# MCU.net
KiCad netlist of a schematic drawn in Altium Designer
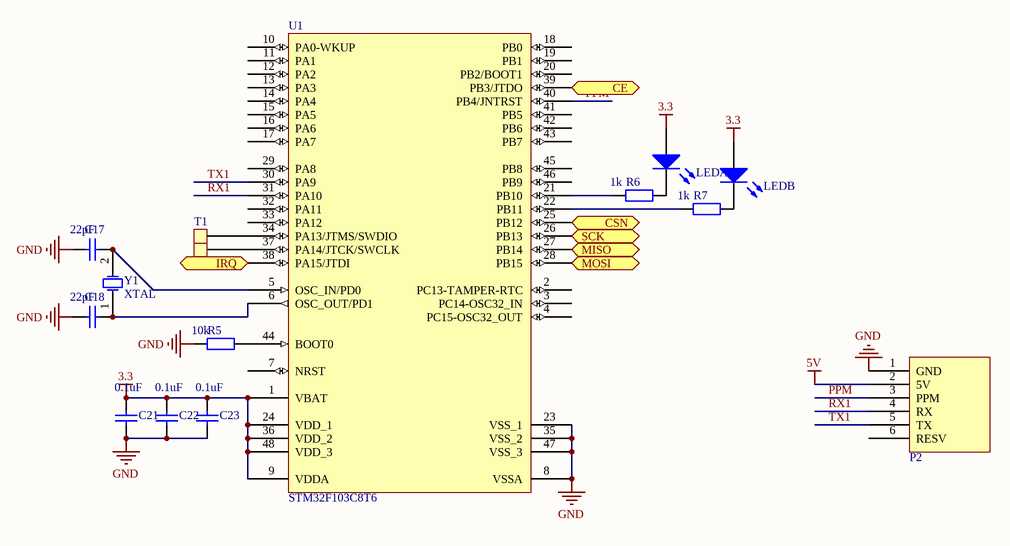
[diagram p0: MCU.SchDoc]

(export (version "E")
  (design (tool "Eeschema 10.0.6"))
  (components
    (comp (ref "C17")
      (value "22pF")
      (footprint "0402")
      (description "Capacitor")
      (fields (field (name "PUBLISHER") "Altium Limited"))
      (libsource (lib "RTC6705") (part "Cap"))
    )
    (comp (ref "C18")
      (value "22pF")
      (footprint "0402")
      (description "Capacitor")
      (fields (field (name "PUBLISHER") "Altium Limited"))
      (libsource (lib "RTC6705") (part "Cap"))
    )
    (comp (ref "C21")
      (value "0.1uF")
      (footprint "0402")
      (description "Capacitor")
      (fields (field (name "PUBLISHER") "Altium Limited"))
      (libsource (lib "RTC6705") (part "Cap"))
    )
    (comp (ref "C22")
      (value "0.1uF")
      (footprint "0402")
      (description "Capacitor")
      (fields (field (name "PUBLISHER") "Altium Limited"))
      (libsource (lib "RTC6705") (part "Cap"))
    )
    (comp (ref "C23")
      (value "0.1uF")
      (footprint "0402")
      (description "Capacitor")
      (fields (field (name "PUBLISHER") "Altium Limited"))
      (libsource (lib "RTC6705") (part "Cap"))
    )
    (comp (ref "LED")
      (value "LEDx2")
      (footprint "LC-0603_Rx2")
      (description "Typical RED GaAs LED")
      (fields (field (name "PUBLISHER") "Altium Limited"))
      (libsource (lib "sch") (part "LEDx2"))
    )
    (comp (ref "P2") (value "PPMInf") (footprint "PPMInf") (libsource (lib "NRF24L01_PA") (part "PPMInf")))
    (comp (ref "R5")
      (value "10k")
      (footprint "0402")
      (description "Resistor")
      (fields (field (name "PUBLISHER") "Altium Limited"))
      (libsource (lib "RTC6705") (part "Res2"))
    )
    (comp (ref "R6")
      (value "1k")
      (footprint "0402")
      (description "Resistor")
      (fields (field (name "PUBLISHER") "Altium Limited"))
      (libsource (lib "RTC6705") (part "Res2"))
    )
    (comp (ref "R7")
      (value "1k")
      (footprint "0402")
      (description "Resistor")
      (fields (field (name "PUBLISHER") "Altium Limited"))
      (libsource (lib "RTC6705") (part "Res2"))
    )
    (comp (ref "T1") (value "TestPad") (footprint "TestPad - 1mm") (libsource (lib "sch") (part "TestPad")))
    (comp (ref "T2") (value "TestPad") (footprint "TestPad - 1mm") (libsource (lib "sch") (part "TestPad")))
    (comp (ref "U1")
      (value "STM32F103C8T6")
      (footprint "LQFP48_L")
      (description "STM32 ARM-based 32-bit MCU with 64 Kbytes Flash, 48-pin LQFP, Industrial Temperature")
      (fields (field (name "PUBLISHER") "*"))
      (libsource (lib "ST Microcontroller 32-Bit STM32 SCH") (part "STM32F103C8T6"))
    )
    (comp (ref "Y1")
      (value "XTAL")
      (footprint "5032-crystal")
      (description "Crystal Oscillator")
      (fields (field (name "PUBLISHER") "Altium Limited"))
      (libsource (lib "Miscellaneous Devices") (part "XTAL"))
    )
  )
  (nets
    (net (code "1") (name "/CE") (class "Default")
      (node (ref "U1") (pin "39") (pinfunction "PB3/JTDO_39") (pintype "bidirectional"))
    )
    (net (code "2") (name "/CSN") (class "Default")
      (node (ref "U1") (pin "25") (pinfunction "PB12_25") (pintype "bidirectional"))
    )
    (net (code "3") (name "/IRQ") (class "Default")
      (node (ref "U1") (pin "38") (pinfunction "PA15/JTDI_38") (pintype "bidirectional"))
    )
    (net (code "4") (name "/MISO") (class "Default")
      (node (ref "U1") (pin "27") (pinfunction "PB14_27") (pintype "bidirectional"))
    )
    (net (code "5") (name "/MOSI") (class "Default")
      (node (ref "U1") (pin "28") (pinfunction "PB15_28") (pintype "bidirectional"))
    )
    (net (code "6") (name "/PPM") (class "Default")
      (node (ref "P2") (pin "3") (pinfunction "PPM_3") (pintype "passive"))
      (node (ref "U1") (pin "40") (pinfunction "PB4/JNTRST_40") (pintype "bidirectional"))
    )
    (net (code "7") (name "/RX1") (class "Default")
      (node (ref "P2") (pin "4") (pinfunction "RX_4") (pintype "passive"))
      (node (ref "U1") (pin "31") (pinfunction "PA10_31") (pintype "bidirectional"))
    )
    (net (code "8") (name "/SCK") (class "Default")
      (node (ref "U1") (pin "26") (pinfunction "PB13_26") (pintype "bidirectional"))
    )
    (net (code "9") (name "/TX1") (class "Default")
      (node (ref "P2") (pin "5") (pinfunction "TX_5") (pintype "passive"))
      (node (ref "U1") (pin "30") (pinfunction "PA9_30") (pintype "bidirectional"))
    )
    (net (code "10") (name "3.3") (class "Default")
      (node (ref "C21") (pin "1") (pinfunction "1_1") (pintype "passive"))
      (node (ref "C22") (pin "1") (pinfunction "1_1") (pintype "passive"))
      (node (ref "C23") (pin "1") (pinfunction "1_1") (pintype "passive"))
      (node (ref "LED") (pin "1") (pinfunction "A_1") (pintype "passive"))
      (node (ref "LED") (pin "2") (pinfunction "A_2") (pintype "passive"))
      (node (ref "U1") (pin "1") (pinfunction "VBAT_1") (pintype "power_in"))
      (node (ref "U1") (pin "24") (pinfunction "VDD_1_24") (pintype "power_in"))
      (node (ref "U1") (pin "36") (pinfunction "VDD_2_36") (pintype "power_in"))
      (node (ref "U1") (pin "48") (pinfunction "VDD_3_48") (pintype "power_in"))
      (node (ref "U1") (pin "9") (pinfunction "VDDA_9") (pintype "power_in"))
    )
    (net (code "11") (name "5V") (class "Default")
      (node (ref "P2") (pin "2") (pinfunction "5V_2") (pintype "passive"))
    )
    (net (code "12") (name "GND") (class "Default")
      (node (ref "C17") (pin "1") (pinfunction "1_1") (pintype "passive"))
      (node (ref "C18") (pin "1") (pinfunction "1_1") (pintype "passive"))
      (node (ref "C21") (pin "2") (pinfunction "2_2") (pintype "passive"))
      (node (ref "C22") (pin "2") (pinfunction "2_2") (pintype "passive"))
      (node (ref "C23") (pin "2") (pinfunction "2_2") (pintype "passive"))
      (node (ref "P2") (pin "1") (pinfunction "GND_1") (pintype "passive"))
      (node (ref "R5") (pin "1") (pinfunction "1_1") (pintype "passive"))
      (node (ref "U1") (pin "23") (pinfunction "VSS_1_23") (pintype "power_in"))
      (node (ref "U1") (pin "35") (pinfunction "VSS_2_35") (pintype "power_in"))
      (node (ref "U1") (pin "47") (pinfunction "VSS_3_47") (pintype "power_in"))
      (node (ref "U1") (pin "8") (pinfunction "VSSA_8") (pintype "power_in"))
    )
    (net (code "13") (name "Net-(LEDA-K)") (class "Default")
      (node (ref "LED") (pin "3") (pinfunction "K_3") (pintype "passive"))
      (node (ref "R6") (pin "2") (pinfunction "2_2") (pintype "passive"))
    )
    (net (code "14") (name "Net-(LEDB-K)") (class "Default")
      (node (ref "LED") (pin "4") (pinfunction "K_4") (pintype "passive"))
      (node (ref "R7") (pin "2") (pinfunction "2_2") (pintype "passive"))
    )
    (net (code "15") (name "Net-(T1-3)") (class "Default")
      (node (ref "T1") (pin "1") (pinfunction "3_1") (pintype "passive"))
      (node (ref "U1") (pin "34") (pinfunction "PA13/JTMS/SWDIO_34") (pintype "bidirectional"))
    )
    (net (code "16") (name "Net-(T2-3)") (class "Default")
      (node (ref "T2") (pin "1") (pinfunction "3_1") (pintype "passive"))
      (node (ref "U1") (pin "37") (pinfunction "PA14/JTCK/SWCLK_37") (pintype "bidirectional"))
    )
    (net (code "17") (name "Net-(U1-BOOT0)") (class "Default")
      (node (ref "R5") (pin "2") (pinfunction "2_2") (pintype "passive"))
      (node (ref "U1") (pin "44") (pinfunction "BOOT0_44") (pintype "input"))
    )
    (net (code "18") (name "Net-(U1-OSC_IN{slash}PD0)") (class "Default")
      (node (ref "C17") (pin "2") (pinfunction "2_2") (pintype "passive"))
      (node (ref "U1") (pin "5") (pinfunction "OSC_IN/PD0_5") (pintype "input"))
      (node (ref "Y1") (pin "2") (pinfunction "OSC2_2") (pintype "passive"))
    )
    (net (code "19") (name "Net-(U1-OSC_OUT{slash}PD1)") (class "Default")
      (node (ref "C18") (pin "2") (pinfunction "2_2") (pintype "passive"))
      (node (ref "U1") (pin "6") (pinfunction "OSC_OUT/PD1_6") (pintype "output"))
      (node (ref "Y1") (pin "1") (pinfunction "OSC1_1") (pintype "passive"))
    )
    (net (code "20") (name "Net-(U1-PB10)") (class "Default")
      (node (ref "R6") (pin "1") (pinfunction "1_1") (pintype "passive"))
      (node (ref "U1") (pin "21") (pinfunction "PB10_21") (pintype "bidirectional"))
    )
    (net (code "21") (name "Net-(U1-PB11)") (class "Default")
      (node (ref "R7") (pin "1") (pinfunction "1_1") (pintype "passive"))
      (node (ref "U1") (pin "22") (pinfunction "PB11_22") (pintype "bidirectional"))
    )
    (net (code "22") (name "unconnected-(P2-RESV-Pad6)") (class "Default")
      (node (ref "P2") (pin "6") (pinfunction "RESV_6") (pintype "passive"))
    )
    (net (code "23") (name "unconnected-(U1-NRST-Pad7)") (class "Default")
      (node (ref "U1") (pin "7") (pinfunction "NRST_7") (pintype "bidirectional"))
    )
    (net (code "24") (name "unconnected-(U1-PA0-WKUP-Pad10)") (class "Default")
      (node (ref "U1") (pin "10") (pinfunction "PA0-WKUP_10") (pintype "bidirectional"))
    )
    (net (code "25") (name "unconnected-(U1-PA1-Pad11)") (class "Default")
      (node (ref "U1") (pin "11") (pinfunction "PA1_11") (pintype "bidirectional"))
    )
    (net (code "26") (name "unconnected-(U1-PA2-Pad12)") (class "Default")
      (node (ref "U1") (pin "12") (pinfunction "PA2_12") (pintype "bidirectional"))
    )
    (net (code "27") (name "unconnected-(U1-PA3-Pad13)") (class "Default")
      (node (ref "U1") (pin "13") (pinfunction "PA3_13") (pintype "bidirectional"))
    )
    (net (code "28") (name "unconnected-(U1-PA4-Pad14)") (class "Default")
      (node (ref "U1") (pin "14") (pinfunction "PA4_14") (pintype "bidirectional"))
    )
    (net (code "29") (name "unconnected-(U1-PA5-Pad15)") (class "Default")
      (node (ref "U1") (pin "15") (pinfunction "PA5_15") (pintype "bidirectional"))
    )
    (net (code "30") (name "unconnected-(U1-PA6-Pad16)") (class "Default")
      (node (ref "U1") (pin "16") (pinfunction "PA6_16") (pintype "bidirectional"))
    )
    (net (code "31") (name "unconnected-(U1-PA7-Pad17)") (class "Default")
      (node (ref "U1") (pin "17") (pinfunction "PA7_17") (pintype "bidirectional"))
    )
    (net (code "32") (name "unconnected-(U1-PA8-Pad29)") (class "Default")
      (node (ref "U1") (pin "29") (pinfunction "PA8_29") (pintype "bidirectional"))
    )
    (net (code "33") (name "unconnected-(U1-PA11-Pad32)") (class "Default")
      (node (ref "U1") (pin "32") (pinfunction "PA11_32") (pintype "bidirectional"))
    )
    (net (code "34") (name "unconnected-(U1-PA12-Pad33)") (class "Default")
      (node (ref "U1") (pin "33") (pinfunction "PA12_33") (pintype "bidirectional"))
    )
    (net (code "35") (name "unconnected-(U1-PB0-Pad18)") (class "Default")
      (node (ref "U1") (pin "18") (pinfunction "PB0_18") (pintype "bidirectional"))
    )
    (net (code "36") (name "unconnected-(U1-PB1-Pad19)") (class "Default")
      (node (ref "U1") (pin "19") (pinfunction "PB1_19") (pintype "bidirectional"))
    )
    (net (code "37") (name "unconnected-(U1-PB2{slash}BOOT1-Pad20)") (class "Default")
      (node (ref "U1") (pin "20") (pinfunction "PB2/BOOT1_20") (pintype "bidirectional"))
    )
    (net (code "38") (name "unconnected-(U1-PB5-Pad41)") (class "Default")
      (node (ref "U1") (pin "41") (pinfunction "PB5_41") (pintype "bidirectional"))
    )
    (net (code "39") (name "unconnected-(U1-PB6-Pad42)") (class "Default")
      (node (ref "U1") (pin "42") (pinfunction "PB6_42") (pintype "bidirectional"))
    )
    (net (code "40") (name "unconnected-(U1-PB7-Pad43)") (class "Default")
      (node (ref "U1") (pin "43") (pinfunction "PB7_43") (pintype "bidirectional"))
    )
    (net (code "41") (name "unconnected-(U1-PB8-Pad45)") (class "Default")
      (node (ref "U1") (pin "45") (pinfunction "PB8_45") (pintype "bidirectional"))
    )
    (net (code "42") (name "unconnected-(U1-PB9-Pad46)") (class "Default")
      (node (ref "U1") (pin "46") (pinfunction "PB9_46") (pintype "bidirectional"))
    )
    (net (code "43") (name "unconnected-(U1-PC13-TAMPER-RTC-Pad2)") (class "Default")
      (node (ref "U1") (pin "2") (pinfunction "PC13-TAMPER-RTC_2") (pintype "bidirectional"))
    )
    (net (code "44") (name "unconnected-(U1-PC14-OSC32_IN-Pad3)") (class "Default")
      (node (ref "U1") (pin "3") (pinfunction "PC14-OSC32_IN_3") (pintype "bidirectional"))
    )
    (net (code "45") (name "unconnected-(U1-PC15-OSC32_OUT-Pad4)") (class "Default")
      (node (ref "U1") (pin "4") (pinfunction "PC15-OSC32_OUT_4") (pintype "bidirectional"))
    )
  )
)
